# Balancer.net
KiCad netlist of a schematic drawn in EAGLE
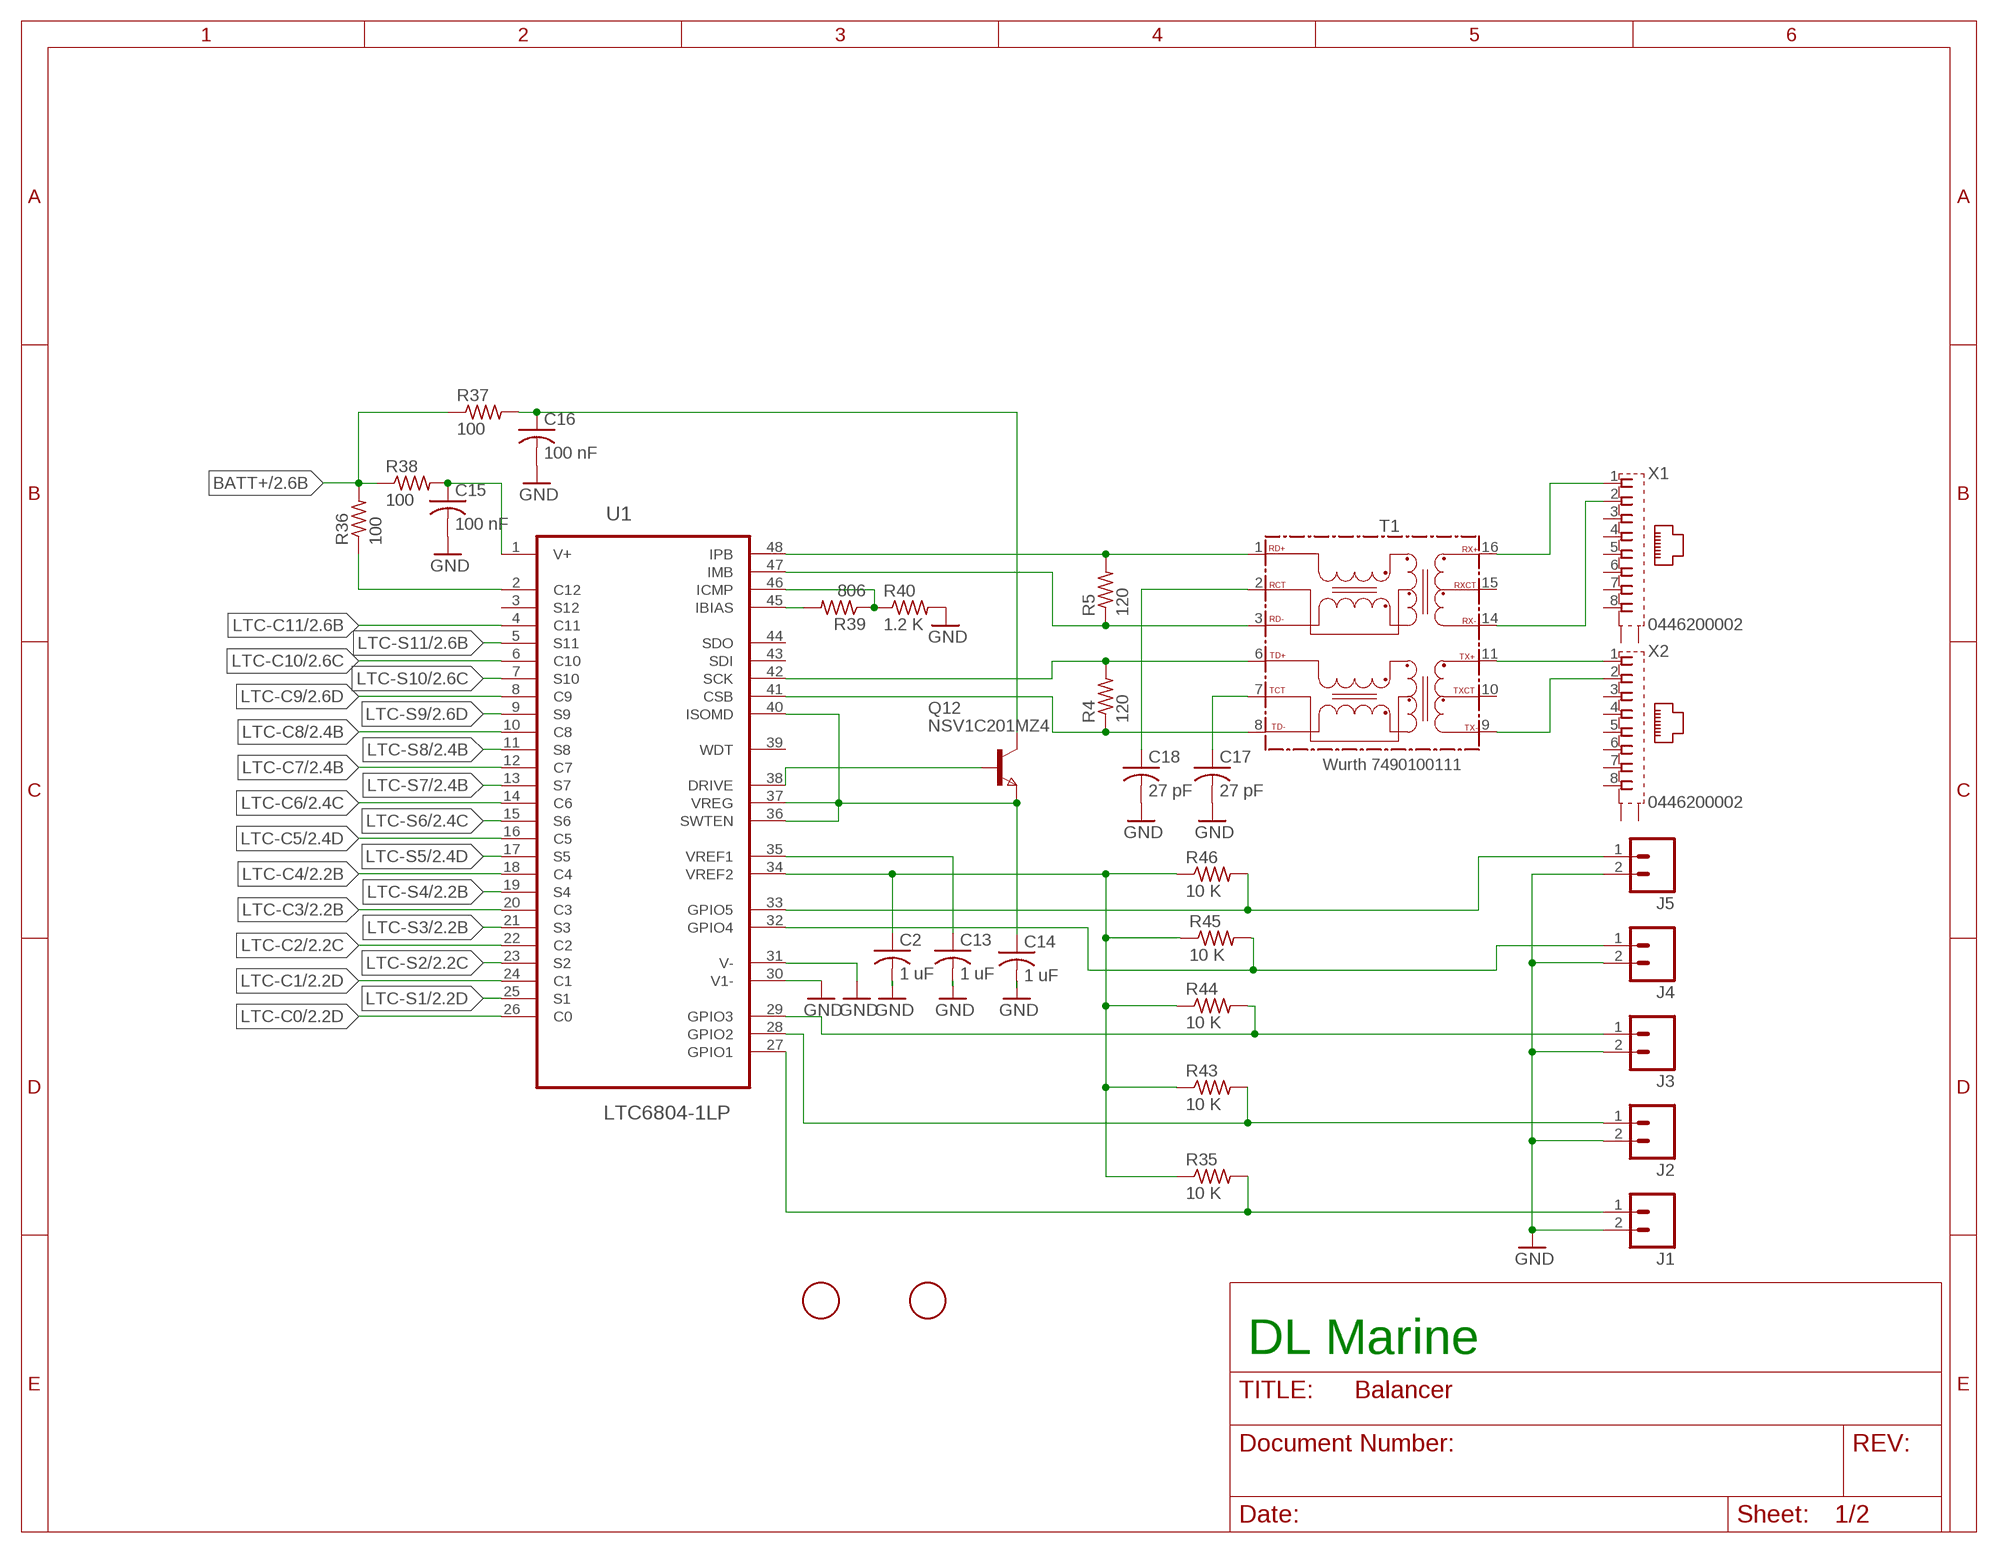
[diagram p0: schematic, sheet 1]
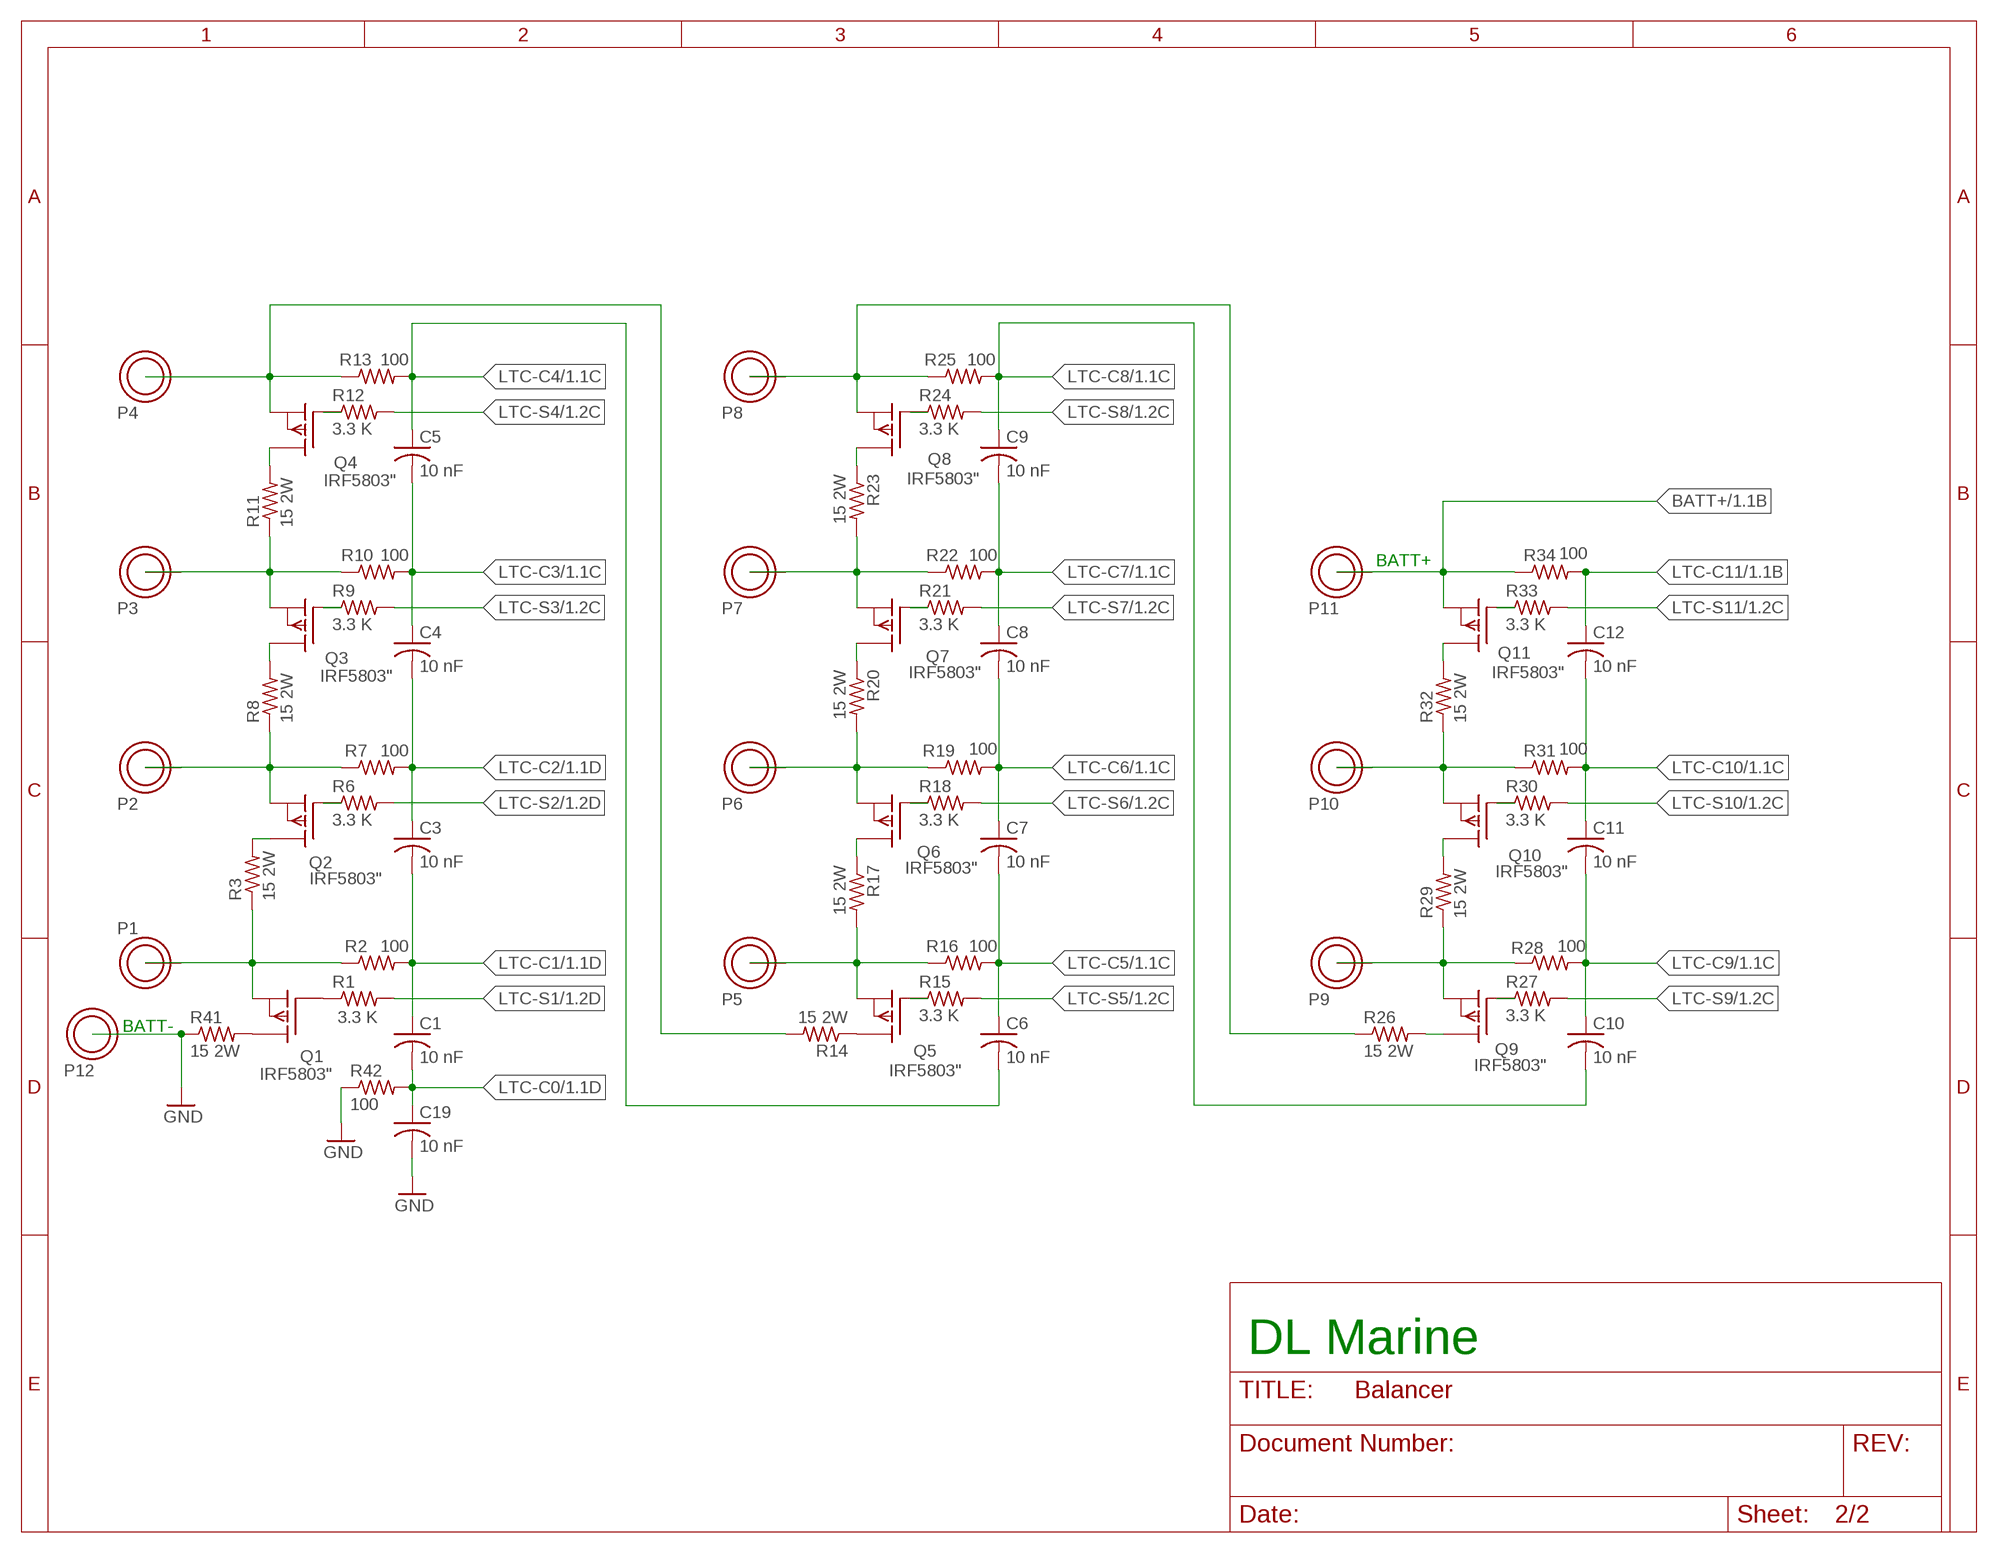
[diagram p1: schematic, sheet 2]

(export (version "E")
  (design (tool "Eeschema 10.0.6"))
  (components
    (comp (ref "C2")
      (value "1 uF")
      (footprint "eagle-import:C0805")
      (libsource (lib "eagle-import") (part "C-USC0805"))
    )
    (comp (ref "C13")
      (value "1 uF")
      (footprint "eagle-import:C0805")
      (libsource (lib "eagle-import") (part "C-USC0805"))
    )
    (comp (ref "C14")
      (value "1 uF")
      (footprint "eagle-import:C0805")
      (libsource (lib "eagle-import") (part "C-USC0805"))
    )
    (comp (ref "C15")
      (value "100 nF")
      (footprint "eagle-import:C0805")
      (libsource (lib "eagle-import") (part "C-USC0805"))
    )
    (comp (ref "C16")
      (value "100 nF")
      (footprint "eagle-import:C0805")
      (libsource (lib "eagle-import") (part "C-USC0805"))
    )
    (comp (ref "C17")
      (value "27 pF")
      (footprint "eagle-import:C0805")
      (libsource (lib "eagle-import") (part "C-USC0805"))
    )
    (comp (ref "C18")
      (value "27 pF")
      (footprint "eagle-import:C0805")
      (libsource (lib "eagle-import") (part "C-USC0805"))
    )
    (comp (ref "J1")
      (value "M02PTH")
      (footprint "eagle-import:1X02")
      (libsource (lib "eagle-import") (part "M02PTH"))
    )
    (comp (ref "J2")
      (value "M02PTH")
      (footprint "eagle-import:1X02")
      (libsource (lib "eagle-import") (part "M02PTH"))
    )
    (comp (ref "J3")
      (value "M02PTH")
      (footprint "eagle-import:1X02")
      (libsource (lib "eagle-import") (part "M02PTH"))
    )
    (comp (ref "J4")
      (value "M02PTH")
      (footprint "eagle-import:1X02")
      (libsource (lib "eagle-import") (part "M02PTH"))
    )
    (comp (ref "J5")
      (value "M02PTH")
      (footprint "eagle-import:1X02")
      (libsource (lib "eagle-import") (part "M02PTH"))
    )
    (comp (ref "Q12")
      (value "NSV1C201MZ4")
      (footprint "eagle-import:SOT223")
      (fields (field (name "MPN") "DJT4031N-13"))
      (libsource (lib "eagle-import") (part "NPNSOT223"))
    )
    (comp (ref "R4")
      (value "120")
      (footprint "eagle-import:R0805")
      (libsource (lib "eagle-import") (part "resistor_R-US_R0805"))
    )
    (comp (ref "R5")
      (value "120")
      (footprint "eagle-import:R0805")
      (libsource (lib "eagle-import") (part "resistor_R-US_R0805"))
    )
    (comp (ref "R35")
      (value "10 K")
      (footprint "eagle-import:R0805")
      (libsource (lib "eagle-import") (part "resistor_R-US_R0805"))
    )
    (comp (ref "R36")
      (value "100")
      (footprint "eagle-import:R0805")
      (libsource (lib "eagle-import") (part "resistor_R-US_R0805"))
    )
    (comp (ref "R37")
      (value "100")
      (footprint "eagle-import:R0805")
      (libsource (lib "eagle-import") (part "resistor_R-US_R0805"))
    )
    (comp (ref "R38")
      (value "100")
      (footprint "eagle-import:R0805")
      (libsource (lib "eagle-import") (part "resistor_R-US_R0805"))
    )
    (comp (ref "R39")
      (value "806")
      (footprint "eagle-import:R0805")
      (libsource (lib "eagle-import") (part "resistor_R-US_R0805"))
    )
    (comp (ref "R40")
      (value "1.2 K")
      (footprint "eagle-import:R0805")
      (libsource (lib "eagle-import") (part "resistor_R-US_R0805"))
    )
    (comp (ref "R43")
      (value "10 K")
      (footprint "eagle-import:R0805")
      (libsource (lib "eagle-import") (part "resistor_R-US_R0805"))
    )
    (comp (ref "R44")
      (value "10 K")
      (footprint "eagle-import:R0805")
      (libsource (lib "eagle-import") (part "resistor_R-US_R0805"))
    )
    (comp (ref "R45")
      (value "10 K")
      (footprint "eagle-import:R0805")
      (libsource (lib "eagle-import") (part "resistor_R-US_R0805"))
    )
    (comp (ref "R46")
      (value "10 K")
      (footprint "eagle-import:R0805")
      (libsource (lib "eagle-import") (part "resistor_R-US_R0805"))
    )
    (comp (ref "T1")
      (value "Wurth 7490100111")
      (footprint "eagle-import:749010011")
      (fields (field (name "MPN") "749010011"))
      (libsource (lib "eagle-import") (part "WE-LAN-10/100-BASE-T,749010011{dblquote}"))
    )
    (comp (ref "U$1")
      (value "FIDUCIAL")
      (footprint "eagle-import:FIDUCIAL_1MM")
      (libsource (lib "eagle-import") (part "FIDUCIAL"))
    )
    (comp (ref "U$2")
      (value "FIDUCIAL")
      (footprint "eagle-import:FIDUCIAL_1MM")
      (libsource (lib "eagle-import") (part "FIDUCIAL"))
    )
    (comp (ref "U1")
      (value "LTC6804-1LP")
      (footprint "eagle-import:SOP50P810X110-48N")
      (libsource (lib "eagle-import") (part "LTC6804-1LP"))
    )
    (comp (ref "X1")
      (value "0446200002")
      (footprint "eagle-import:0446200002")
      (fields (field (name "MF") "MOLEX"))
      (libsource (lib "eagle-import") (part "0446200002"))
    )
    (comp (ref "X2")
      (value "0446200002")
      (footprint "eagle-import:0446200002")
      (fields (field (name "MF") "MOLEX"))
      (libsource (lib "eagle-import") (part "0446200002"))
    )
    (comp (ref "C1")
      (value "10 nF")
      (footprint "eagle-import:C0805")
      (libsource (lib "eagle-import") (part "C-USC0805"))
    )
    (comp (ref "C3")
      (value "10 nF")
      (footprint "eagle-import:C0805")
      (libsource (lib "eagle-import") (part "C-USC0805"))
    )
    (comp (ref "C4")
      (value "10 nF")
      (footprint "eagle-import:C0805")
      (libsource (lib "eagle-import") (part "C-USC0805"))
    )
    (comp (ref "C5")
      (value "10 nF")
      (footprint "eagle-import:C0805")
      (libsource (lib "eagle-import") (part "C-USC0805"))
    )
    (comp (ref "C6")
      (value "10 nF")
      (footprint "eagle-import:C0805")
      (libsource (lib "eagle-import") (part "C-USC0805"))
    )
    (comp (ref "C7")
      (value "10 nF")
      (footprint "eagle-import:C0805")
      (libsource (lib "eagle-import") (part "C-USC0805"))
    )
    (comp (ref "C8")
      (value "10 nF")
      (footprint "eagle-import:C0805")
      (libsource (lib "eagle-import") (part "C-USC0805"))
    )
    (comp (ref "C9")
      (value "10 nF")
      (footprint "eagle-import:C0805")
      (libsource (lib "eagle-import") (part "C-USC0805"))
    )
    (comp (ref "C10")
      (value "10 nF")
      (footprint "eagle-import:C0805")
      (libsource (lib "eagle-import") (part "C-USC0805"))
    )
    (comp (ref "C11")
      (value "10 nF")
      (footprint "eagle-import:C0805")
      (libsource (lib "eagle-import") (part "C-USC0805"))
    )
    (comp (ref "C12")
      (value "10 nF")
      (footprint "eagle-import:C0805")
      (libsource (lib "eagle-import") (part "C-USC0805"))
    )
    (comp (ref "C19")
      (value "10 nF")
      (footprint "eagle-import:C0805")
      (libsource (lib "eagle-import") (part "C-USC0805"))
    )
    (comp (ref "P1")
      (value "CONN-CELL")
      (footprint "eagle-import:CONN-CELL")
      (libsource (lib "eagle-import") (part "CONN-CELL"))
    )
    (comp (ref "P2")
      (value "CONN-CELL")
      (footprint "eagle-import:CONN-CELL")
      (libsource (lib "eagle-import") (part "CONN-CELL"))
    )
    (comp (ref "P3")
      (value "CONN-CELL")
      (footprint "eagle-import:CONN-CELL")
      (libsource (lib "eagle-import") (part "CONN-CELL"))
    )
    (comp (ref "P4")
      (value "CONN-CELL")
      (footprint "eagle-import:CONN-CELL")
      (libsource (lib "eagle-import") (part "CONN-CELL"))
    )
    (comp (ref "P5")
      (value "CONN-CELL")
      (footprint "eagle-import:CONN-CELL")
      (libsource (lib "eagle-import") (part "CONN-CELL"))
    )
    (comp (ref "P6")
      (value "CONN-CELL")
      (footprint "eagle-import:CONN-CELL")
      (libsource (lib "eagle-import") (part "CONN-CELL"))
    )
    (comp (ref "P7")
      (value "CONN-CELL")
      (footprint "eagle-import:CONN-CELL")
      (libsource (lib "eagle-import") (part "CONN-CELL"))
    )
    (comp (ref "P8")
      (value "CONN-CELL")
      (footprint "eagle-import:CONN-CELL")
      (libsource (lib "eagle-import") (part "CONN-CELL"))
    )
    (comp (ref "P9")
      (value "CONN-CELL")
      (footprint "eagle-import:CONN-CELL")
      (libsource (lib "eagle-import") (part "CONN-CELL"))
    )
    (comp (ref "P10")
      (value "CONN-CELL")
      (footprint "eagle-import:CONN-CELL")
      (libsource (lib "eagle-import") (part "CONN-CELL"))
    )
    (comp (ref "P11")
      (value "CONN-CELL")
      (footprint "eagle-import:CONN-CELL")
      (libsource (lib "eagle-import") (part "CONN-CELL"))
    )
    (comp (ref "P12")
      (value "CONN-CELL")
      (footprint "eagle-import:CONN-CELL")
      (libsource (lib "eagle-import") (part "CONN-CELL"))
    )
    (comp (ref "Q1")
      (value "IRF5803\"")
      (footprint "eagle-import:TSOP6_SOT457")
      (libsource (lib "eagle-import") (part "IRF5803{dblquote}"))
    )
    (comp (ref "Q2")
      (value "IRF5803\"")
      (footprint "eagle-import:TSOP6_SOT457")
      (libsource (lib "eagle-import") (part "IRF5803{dblquote}"))
    )
    (comp (ref "Q3")
      (value "IRF5803\"")
      (footprint "eagle-import:TSOP6_SOT457")
      (libsource (lib "eagle-import") (part "IRF5803{dblquote}"))
    )
    (comp (ref "Q4")
      (value "IRF5803\"")
      (footprint "eagle-import:TSOP6_SOT457")
      (libsource (lib "eagle-import") (part "IRF5803{dblquote}"))
    )
    (comp (ref "Q5")
      (value "IRF5803\"")
      (footprint "eagle-import:TSOP6_SOT457")
      (libsource (lib "eagle-import") (part "IRF5803{dblquote}"))
    )
    (comp (ref "Q6")
      (value "IRF5803\"")
      (footprint "eagle-import:TSOP6_SOT457")
      (libsource (lib "eagle-import") (part "IRF5803{dblquote}"))
    )
    (comp (ref "Q7")
      (value "IRF5803\"")
      (footprint "eagle-import:TSOP6_SOT457")
      (libsource (lib "eagle-import") (part "IRF5803{dblquote}"))
    )
    (comp (ref "Q8")
      (value "IRF5803\"")
      (footprint "eagle-import:TSOP6_SOT457")
      (libsource (lib "eagle-import") (part "IRF5803{dblquote}"))
    )
    (comp (ref "Q9")
      (value "IRF5803\"")
      (footprint "eagle-import:TSOP6_SOT457")
      (libsource (lib "eagle-import") (part "IRF5803{dblquote}"))
    )
    (comp (ref "Q10")
      (value "IRF5803\"")
      (footprint "eagle-import:TSOP6_SOT457")
      (libsource (lib "eagle-import") (part "IRF5803{dblquote}"))
    )
    (comp (ref "Q11")
      (value "IRF5803\"")
      (footprint "eagle-import:TSOP6_SOT457")
      (libsource (lib "eagle-import") (part "IRF5803{dblquote}"))
    )
    (comp (ref "R1")
      (value "3.3 K")
      (footprint "eagle-import:R0805")
      (libsource (lib "eagle-import") (part "resistor_R-US_R0805"))
    )
    (comp (ref "R2")
      (value "100")
      (footprint "eagle-import:R0805")
      (libsource (lib "eagle-import") (part "resistor_R-US_R0805"))
    )
    (comp (ref "R3")
      (value "15 2W")
      (footprint "eagle-import:R2512L")
      (libsource (lib "eagle-import") (part "R-US_R2512"))
    )
    (comp (ref "R6")
      (value "3.3 K")
      (footprint "eagle-import:R0805")
      (libsource (lib "eagle-import") (part "resistor_R-US_R0805"))
    )
    (comp (ref "R7")
      (value "100")
      (footprint "eagle-import:R0805")
      (libsource (lib "eagle-import") (part "resistor_R-US_R0805"))
    )
    (comp (ref "R8")
      (value "15 2W")
      (footprint "eagle-import:R2512L")
      (libsource (lib "eagle-import") (part "R-US_R2512"))
    )
    (comp (ref "R9")
      (value "3.3 K")
      (footprint "eagle-import:R0805")
      (libsource (lib "eagle-import") (part "resistor_R-US_R0805"))
    )
    (comp (ref "R10")
      (value "100")
      (footprint "eagle-import:R0805")
      (libsource (lib "eagle-import") (part "resistor_R-US_R0805"))
    )
    (comp (ref "R11")
      (value "15 2W")
      (footprint "eagle-import:R2512L")
      (libsource (lib "eagle-import") (part "R-US_R2512"))
    )
    (comp (ref "R12")
      (value "3.3 K")
      (footprint "eagle-import:R0805")
      (libsource (lib "eagle-import") (part "resistor_R-US_R0805"))
    )
    (comp (ref "R13")
      (value "100")
      (footprint "eagle-import:R0805")
      (libsource (lib "eagle-import") (part "resistor_R-US_R0805"))
    )
    (comp (ref "R14")
      (value "15 2W")
      (footprint "eagle-import:R2512L")
      (libsource (lib "eagle-import") (part "R-US_R2512"))
    )
    (comp (ref "R15")
      (value "3.3 K")
      (footprint "eagle-import:R0805")
      (libsource (lib "eagle-import") (part "resistor_R-US_R0805"))
    )
    (comp (ref "R16")
      (value "100")
      (footprint "eagle-import:R0805")
      (libsource (lib "eagle-import") (part "resistor_R-US_R0805"))
    )
    (comp (ref "R17")
      (value "15 2W")
      (footprint "eagle-import:R2512L")
      (libsource (lib "eagle-import") (part "R-US_R2512"))
    )
    (comp (ref "R18")
      (value "3.3 K")
      (footprint "eagle-import:R0805")
      (libsource (lib "eagle-import") (part "resistor_R-US_R0805"))
    )
    (comp (ref "R19")
      (value "100")
      (footprint "eagle-import:R0805")
      (libsource (lib "eagle-import") (part "resistor_R-US_R0805"))
    )
    (comp (ref "R20")
      (value "15 2W")
      (footprint "eagle-import:R2512L")
      (libsource (lib "eagle-import") (part "R-US_R2512"))
    )
    (comp (ref "R21")
      (value "3.3 K")
      (footprint "eagle-import:R0805")
      (libsource (lib "eagle-import") (part "resistor_R-US_R0805"))
    )
    (comp (ref "R22")
      (value "100")
      (footprint "eagle-import:R0805")
      (libsource (lib "eagle-import") (part "resistor_R-US_R0805"))
    )
    (comp (ref "R23")
      (value "15 2W")
      (footprint "eagle-import:R2512L")
      (libsource (lib "eagle-import") (part "R-US_R2512"))
    )
    (comp (ref "R24")
      (value "3.3 K")
      (footprint "eagle-import:R0805")
      (libsource (lib "eagle-import") (part "resistor_R-US_R0805"))
    )
    (comp (ref "R25")
      (value "100")
      (footprint "eagle-import:R0805")
      (libsource (lib "eagle-import") (part "resistor_R-US_R0805"))
    )
    (comp (ref "R26")
      (value "15 2W")
      (footprint "eagle-import:R2512L")
      (libsource (lib "eagle-import") (part "R-US_R2512"))
    )
    (comp (ref "R27")
      (value "3.3 K")
      (footprint "eagle-import:R0805")
      (libsource (lib "eagle-import") (part "resistor_R-US_R0805"))
    )
    (comp (ref "R28")
      (value "100")
      (footprint "eagle-import:R0805")
      (libsource (lib "eagle-import") (part "resistor_R-US_R0805"))
    )
    (comp (ref "R29")
      (value "15 2W")
      (footprint "eagle-import:R2512L")
      (libsource (lib "eagle-import") (part "R-US_R2512"))
    )
    (comp (ref "R30")
      (value "3.3 K")
      (footprint "eagle-import:R0805")
      (libsource (lib "eagle-import") (part "resistor_R-US_R0805"))
    )
    (comp (ref "R31")
      (value "100")
      (footprint "eagle-import:R0805")
      (libsource (lib "eagle-import") (part "resistor_R-US_R0805"))
    )
    (comp (ref "R32")
      (value "15 2W")
      (footprint "eagle-import:R2512L")
      (libsource (lib "eagle-import") (part "R-US_R2512"))
    )
    (comp (ref "R33")
      (value "3.3 K")
      (footprint "eagle-import:R0805")
      (libsource (lib "eagle-import") (part "resistor_R-US_R0805"))
    )
    (comp (ref "R34")
      (value "100")
      (footprint "eagle-import:R0805")
      (libsource (lib "eagle-import") (part "resistor_R-US_R0805"))
    )
    (comp (ref "R41")
      (value "15 2W")
      (footprint "eagle-import:R2512L")
      (libsource (lib "eagle-import") (part "R-US_R2512"))
    )
    (comp (ref "R42")
      (value "100")
      (footprint "eagle-import:R0805")
      (libsource (lib "eagle-import") (part "resistor_R-US_R0805"))
    )
  )
  (nets
    (net (code "1") (name "BATT+") (class "Default")
      (node (ref "P11") (pin "P$1") (pinfunction "P$1_P$1") (pintype "bidirectional"))
      (node (ref "Q11") (pin "P$4") (pinfunction "S_P$4") (pintype "passive"))
      (node (ref "R34") (pin "1") (pinfunction "1_1") (pintype "passive"))
      (node (ref "R36") (pin "2") (pinfunction "2_2") (pintype "passive"))
      (node (ref "R37") (pin "1") (pinfunction "1_1") (pintype "passive"))
      (node (ref "R38") (pin "1") (pinfunction "1_1") (pintype "passive"))
    )
    (net (code "2") (name "GND") (class "Default")
      (node (ref "C13") (pin "2") (pinfunction "2_2") (pintype "passive"))
      (node (ref "C14") (pin "2") (pinfunction "2_2") (pintype "passive"))
      (node (ref "C15") (pin "2") (pinfunction "2_2") (pintype "passive"))
      (node (ref "C16") (pin "2") (pinfunction "2_2") (pintype "passive"))
      (node (ref "C17") (pin "2") (pinfunction "2_2") (pintype "passive"))
      (node (ref "C18") (pin "2") (pinfunction "2_2") (pintype "passive"))
      (node (ref "C19") (pin "2") (pinfunction "2_2") (pintype "passive"))
      (node (ref "C2") (pin "2") (pinfunction "2_2") (pintype "passive"))
      (node (ref "J1") (pin "2") (pinfunction "2_2") (pintype "passive"))
      (node (ref "J2") (pin "2") (pinfunction "2_2") (pintype "passive"))
      (node (ref "J3") (pin "2") (pinfunction "2_2") (pintype "passive"))
      (node (ref "J4") (pin "2") (pinfunction "2_2") (pintype "passive"))
      (node (ref "J5") (pin "2") (pinfunction "2_2") (pintype "passive"))
      (node (ref "P12") (pin "P$1") (pinfunction "P$1_P$1") (pintype "bidirectional"))
      (node (ref "R40") (pin "2") (pinfunction "2_2") (pintype "passive"))
      (node (ref "R41") (pin "1") (pinfunction "1_1") (pintype "passive"))
      (node (ref "R42") (pin "1") (pinfunction "1_1") (pintype "passive"))
      (node (ref "U1") (pin "30") (pinfunction "V1-_30") (pintype "power_in"))
      (node (ref "U1") (pin "31") (pinfunction "V-_31") (pintype "power_in"))
    )
    (net (code "3") (name "LTC-C0") (class "Default")
      (node (ref "C1") (pin "2") (pinfunction "2_2") (pintype "passive"))
      (node (ref "C19") (pin "1") (pinfunction "1_1") (pintype "passive"))
      (node (ref "R42") (pin "2") (pinfunction "2_2") (pintype "passive"))
      (node (ref "U1") (pin "26") (pinfunction "C0_26") (pintype "input"))
    )
    (net (code "4") (name "LTC-C1") (class "Default")
      (node (ref "C1") (pin "1") (pinfunction "1_1") (pintype "passive"))
      (node (ref "C3") (pin "2") (pinfunction "2_2") (pintype "passive"))
      (node (ref "R2") (pin "2") (pinfunction "2_2") (pintype "passive"))
      (node (ref "U1") (pin "24") (pinfunction "C1_24") (pintype "input"))
    )
    (net (code "5") (name "LTC-C2") (class "Default")
      (node (ref "C3") (pin "1") (pinfunction "1_1") (pintype "passive"))
      (node (ref "C4") (pin "2") (pinfunction "2_2") (pintype "passive"))
      (node (ref "R7") (pin "2") (pinfunction "2_2") (pintype "passive"))
      (node (ref "U1") (pin "22") (pinfunction "C2_22") (pintype "input"))
    )
    (net (code "6") (name "LTC-C3") (class "Default")
      (node (ref "C4") (pin "1") (pinfunction "1_1") (pintype "passive"))
      (node (ref "C5") (pin "2") (pinfunction "2_2") (pintype "passive"))
      (node (ref "R10") (pin "2") (pinfunction "2_2") (pintype "passive"))
      (node (ref "U1") (pin "20") (pinfunction "C3_20") (pintype "input"))
    )
    (net (code "7") (name "LTC-C4") (class "Default")
      (node (ref "C5") (pin "1") (pinfunction "1_1") (pintype "passive"))
      (node (ref "C6") (pin "2") (pinfunction "2_2") (pintype "passive"))
      (node (ref "R13") (pin "2") (pinfunction "2_2") (pintype "passive"))
      (node (ref "U1") (pin "18") (pinfunction "C4_18") (pintype "input"))
    )
    (net (code "8") (name "LTC-C5") (class "Default")
      (node (ref "C6") (pin "1") (pinfunction "1_1") (pintype "passive"))
      (node (ref "C7") (pin "2") (pinfunction "2_2") (pintype "passive"))
      (node (ref "R16") (pin "2") (pinfunction "2_2") (pintype "passive"))
      (node (ref "U1") (pin "16") (pinfunction "C5_16") (pintype "input"))
    )
    (net (code "9") (name "LTC-C6") (class "Default")
      (node (ref "C7") (pin "1") (pinfunction "1_1") (pintype "passive"))
      (node (ref "C8") (pin "2") (pinfunction "2_2") (pintype "passive"))
      (node (ref "R19") (pin "2") (pinfunction "2_2") (pintype "passive"))
      (node (ref "U1") (pin "14") (pinfunction "C6_14") (pintype "input"))
    )
    (net (code "10") (name "LTC-C7") (class "Default")
      (node (ref "C8") (pin "1") (pinfunction "1_1") (pintype "passive"))
      (node (ref "C9") (pin "2") (pinfunction "2_2") (pintype "passive"))
      (node (ref "R22") (pin "2") (pinfunction "2_2") (pintype "passive"))
      (node (ref "U1") (pin "12") (pinfunction "C7_12") (pintype "input"))
    )
    (net (code "11") (name "LTC-C8") (class "Default")
      (node (ref "C10") (pin "2") (pinfunction "2_2") (pintype "passive"))
      (node (ref "C9") (pin "1") (pinfunction "1_1") (pintype "passive"))
      (node (ref "R25") (pin "2") (pinfunction "2_2") (pintype "passive"))
      (node (ref "U1") (pin "10") (pinfunction "C8_10") (pintype "input"))
    )
    (net (code "12") (name "LTC-C9") (class "Default")
      (node (ref "C10") (pin "1") (pinfunction "1_1") (pintype "passive"))
      (node (ref "C11") (pin "2") (pinfunction "2_2") (pintype "passive"))
      (node (ref "R28") (pin "2") (pinfunction "2_2") (pintype "passive"))
      (node (ref "U1") (pin "8") (pinfunction "C9_8") (pintype "input"))
    )
    (net (code "13") (name "LTC-C10") (class "Default")
      (node (ref "C11") (pin "1") (pinfunction "1_1") (pintype "passive"))
      (node (ref "C12") (pin "2") (pinfunction "2_2") (pintype "passive"))
      (node (ref "R31") (pin "2") (pinfunction "2_2") (pintype "passive"))
      (node (ref "U1") (pin "6") (pinfunction "C10_6") (pintype "input"))
    )
    (net (code "14") (name "LTC-C11") (class "Default")
      (node (ref "C12") (pin "1") (pinfunction "1_1") (pintype "passive"))
      (node (ref "R34") (pin "2") (pinfunction "2_2") (pintype "passive"))
      (node (ref "U1") (pin "4") (pinfunction "C11_4") (pintype "input"))
    )
    (net (code "15") (name "LTC-S1") (class "Default")
      (node (ref "R1") (pin "2") (pinfunction "2_2") (pintype "passive"))
      (node (ref "U1") (pin "25") (pinfunction "S1_25") (pintype "output"))
    )
    (net (code "16") (name "LTC-S2") (class "Default")
      (node (ref "R6") (pin "2") (pinfunction "2_2") (pintype "passive"))
      (node (ref "U1") (pin "23") (pinfunction "S2_23") (pintype "output"))
    )
    (net (code "17") (name "LTC-S3") (class "Default")
      (node (ref "R9") (pin "2") (pinfunction "2_2") (pintype "passive"))
      (node (ref "U1") (pin "21") (pinfunction "S3_21") (pintype "output"))
    )
    (net (code "18") (name "LTC-S4") (class "Default")
      (node (ref "R12") (pin "2") (pinfunction "2_2") (pintype "passive"))
      (node (ref "U1") (pin "19") (pinfunction "S4_19") (pintype "output"))
    )
    (net (code "19") (name "LTC-S5") (class "Default")
      (node (ref "R15") (pin "2") (pinfunction "2_2") (pintype "passive"))
      (node (ref "U1") (pin "17") (pinfunction "S5_17") (pintype "output"))
    )
    (net (code "20") (name "LTC-S6") (class "Default")
      (node (ref "R18") (pin "2") (pinfunction "2_2") (pintype "passive"))
      (node (ref "U1") (pin "15") (pinfunction "S6_15") (pintype "output"))
    )
    (net (code "21") (name "LTC-S7") (class "Default")
      (node (ref "R21") (pin "2") (pinfunction "2_2") (pintype "passive"))
      (node (ref "U1") (pin "13") (pinfunction "S7_13") (pintype "output"))
    )
    (net (code "22") (name "LTC-S8") (class "Default")
      (node (ref "R24") (pin "2") (pinfunction "2_2") (pintype "passive"))
      (node (ref "U1") (pin "11") (pinfunction "S8_11") (pintype "output"))
    )
    (net (code "23") (name "LTC-S9") (class "Default")
      (node (ref "R27") (pin "2") (pinfunction "2_2") (pintype "passive"))
      (node (ref "U1") (pin "9") (pinfunction "S9_9") (pintype "output"))
    )
    (net (code "24") (name "LTC-S10") (class "Default")
      (node (ref "R30") (pin "2") (pinfunction "2_2") (pintype "passive"))
      (node (ref "U1") (pin "7") (pinfunction "S10_7") (pintype "output"))
    )
    (net (code "25") (name "LTC-S11") (class "Default")
      (node (ref "R33") (pin "2") (pinfunction "2_2") (pintype "passive"))
      (node (ref "U1") (pin "5") (pinfunction "S11_5") (pintype "output"))
    )
    (net (code "26") (name "Net-(C16-Pad1)") (class "Default")
      (node (ref "C16") (pin "1") (pinfunction "1_1") (pintype "passive"))
      (node (ref "Q12") (pin "2") (pinfunction "C_2") (pintype "passive"))
      (node (ref "Q12") (pin "4") (pinfunction "C_4") (pintype "passive"))
      (node (ref "R37") (pin "2") (pinfunction "2_2") (pintype "passive"))
    )
    (net (code "27") (name "Net-(Q1-D-PadP$1)") (class "Default")
      (node (ref "Q1") (pin "P$1") (pinfunction "D_P$1") (pintype "passive"))
      (node (ref "Q1") (pin "P$2") (pinfunction "D_P$2") (pintype "passive"))
      (node (ref "Q1") (pin "P$5") (pinfunction "D_P$5") (pintype "passive"))
      (node (ref "Q1") (pin "P$6") (pinfunction "D_P$6") (pintype "passive"))
      (node (ref "R41") (pin "2") (pinfunction "2_2") (pintype "passive"))
    )
    (net (code "28") (name "Net-(Q1-G)") (class "Default")
      (node (ref "Q1") (pin "P$3") (pinfunction "G_P$3") (pintype "passive"))
      (node (ref "R1") (pin "1") (pinfunction "1_1") (pintype "passive"))
    )
    (net (code "29") (name "Net-(Q1-S)") (class "Default")
      (node (ref "P1") (pin "P$1") (pinfunction "P$1_P$1") (pintype "bidirectional"))
      (node (ref "Q1") (pin "P$4") (pinfunction "S_P$4") (pintype "passive"))
      (node (ref "R2") (pin "1") (pinfunction "1_1") (pintype "passive"))
      (node (ref "R3") (pin "1") (pinfunction "1_1") (pintype "passive"))
    )
    (net (code "30") (name "Net-(Q2-D-PadP$1)") (class "Default")
      (node (ref "Q2") (pin "P$1") (pinfunction "D_P$1") (pintype "passive"))
      (node (ref "Q2") (pin "P$2") (pinfunction "D_P$2") (pintype "passive"))
      (node (ref "Q2") (pin "P$5") (pinfunction "D_P$5") (pintype "passive"))
      (node (ref "Q2") (pin "P$6") (pinfunction "D_P$6") (pintype "passive"))
      (node (ref "R3") (pin "2") (pinfunction "2_2") (pintype "passive"))
    )
    (net (code "31") (name "Net-(Q2-G)") (class "Default")
      (node (ref "Q2") (pin "P$3") (pinfunction "G_P$3") (pintype "passive"))
      (node (ref "R6") (pin "1") (pinfunction "1_1") (pintype "passive"))
    )
    (net (code "32") (name "Net-(Q2-S)") (class "Default")
      (node (ref "P2") (pin "P$1") (pinfunction "P$1_P$1") (pintype "bidirectional"))
      (node (ref "Q2") (pin "P$4") (pinfunction "S_P$4") (pintype "passive"))
      (node (ref "R7") (pin "1") (pinfunction "1_1") (pintype "passive"))
      (node (ref "R8") (pin "1") (pinfunction "1_1") (pintype "passive"))
    )
    (net (code "33") (name "Net-(Q3-D-PadP$1)") (class "Default")
      (node (ref "Q3") (pin "P$1") (pinfunction "D_P$1") (pintype "passive"))
      (node (ref "Q3") (pin "P$2") (pinfunction "D_P$2") (pintype "passive"))
      (node (ref "Q3") (pin "P$5") (pinfunction "D_P$5") (pintype "passive"))
      (node (ref "Q3") (pin "P$6") (pinfunction "D_P$6") (pintype "passive"))
      (node (ref "R8") (pin "2") (pinfunction "2_2") (pintype "passive"))
    )
    (net (code "34") (name "Net-(Q3-G)") (class "Default")
      (node (ref "Q3") (pin "P$3") (pinfunction "G_P$3") (pintype "passive"))
      (node (ref "R9") (pin "1") (pinfunction "1_1") (pintype "passive"))
    )
    (net (code "35") (name "Net-(Q3-S)") (class "Default")
      (node (ref "P3") (pin "P$1") (pinfunction "P$1_P$1") (pintype "bidirectional"))
      (node (ref "Q3") (pin "P$4") (pinfunction "S_P$4") (pintype "passive"))
      (node (ref "R10") (pin "1") (pinfunction "1_1") (pintype "passive"))
      (node (ref "R11") (pin "1") (pinfunction "1_1") (pintype "passive"))
    )
    (net (code "36") (name "Net-(Q4-D-PadP$1)") (class "Default")
      (node (ref "Q4") (pin "P$1") (pinfunction "D_P$1") (pintype "passive"))
      (node (ref "Q4") (pin "P$2") (pinfunction "D_P$2") (pintype "passive"))
      (node (ref "Q4") (pin "P$5") (pinfunction "D_P$5") (pintype "passive"))
      (node (ref "Q4") (pin "P$6") (pinfunction "D_P$6") (pintype "passive"))
      (node (ref "R11") (pin "2") (pinfunction "2_2") (pintype "passive"))
    )
    (net (code "37") (name "Net-(Q4-G)") (class "Default")
      (node (ref "Q4") (pin "P$3") (pinfunction "G_P$3") (pintype "passive"))
      (node (ref "R12") (pin "1") (pinfunction "1_1") (pintype "passive"))
    )
    (net (code "38") (name "Net-(Q4-S)") (class "Default")
      (node (ref "P4") (pin "P$1") (pinfunction "P$1_P$1") (pintype "bidirectional"))
      (node (ref "Q4") (pin "P$4") (pinfunction "S_P$4") (pintype "passive"))
      (node (ref "R13") (pin "1") (pinfunction "1_1") (pintype "passive"))
      (node (ref "R14") (pin "2") (pinfunction "2_2") (pintype "passive"))
    )
    (net (code "39") (name "Net-(Q5-D-PadP$1)") (class "Default")
      (node (ref "Q5") (pin "P$1") (pinfunction "D_P$1") (pintype "passive"))
      (node (ref "Q5") (pin "P$2") (pinfunction "D_P$2") (pintype "passive"))
      (node (ref "Q5") (pin "P$5") (pinfunction "D_P$5") (pintype "passive"))
      (node (ref "Q5") (pin "P$6") (pinfunction "D_P$6") (pintype "passive"))
      (node (ref "R14") (pin "1") (pinfunction "1_1") (pintype "passive"))
    )
    (net (code "40") (name "Net-(Q5-G)") (class "Default")
      (node (ref "Q5") (pin "P$3") (pinfunction "G_P$3") (pintype "passive"))
      (node (ref "R15") (pin "1") (pinfunction "1_1") (pintype "passive"))
    )
    (net (code "41") (name "Net-(Q5-S)") (class "Default")
      (node (ref "P5") (pin "P$1") (pinfunction "P$1_P$1") (pintype "bidirectional"))
      (node (ref "Q5") (pin "P$4") (pinfunction "S_P$4") (pintype "passive"))
      (node (ref "R16") (pin "1") (pinfunction "1_1") (pintype "passive"))
      (node (ref "R17") (pin "2") (pinfunction "2_2") (pintype "passive"))
    )
    (net (code "42") (name "Net-(Q6-D-PadP$1)") (class "Default")
      (node (ref "Q6") (pin "P$1") (pinfunction "D_P$1") (pintype "passive"))
      (node (ref "Q6") (pin "P$2") (pinfunction "D_P$2") (pintype "passive"))
      (node (ref "Q6") (pin "P$5") (pinfunction "D_P$5") (pintype "passive"))
      (node (ref "Q6") (pin "P$6") (pinfunction "D_P$6") (pintype "passive"))
      (node (ref "R17") (pin "1") (pinfunction "1_1") (pintype "passive"))
    )
    (net (code "43") (name "Net-(Q6-G)") (class "Default")
      (node (ref "Q6") (pin "P$3") (pinfunction "G_P$3") (pintype "passive"))
      (node (ref "R18") (pin "1") (pinfunction "1_1") (pintype "passive"))
    )
    (net (code "44") (name "Net-(Q6-S)") (class "Default")
      (node (ref "P6") (pin "P$1") (pinfunction "P$1_P$1") (pintype "bidirectional"))
      (node (ref "Q6") (pin "P$4") (pinfunction "S_P$4") (pintype "passive"))
      (node (ref "R19") (pin "1") (pinfunction "1_1") (pintype "passive"))
      (node (ref "R20") (pin "2") (pinfunction "2_2") (pintype "passive"))
    )
    (net (code "45") (name "Net-(Q7-D-PadP$1)") (class "Default")
      (node (ref "Q7") (pin "P$1") (pinfunction "D_P$1") (pintype "passive"))
      (node (ref "Q7") (pin "P$2") (pinfunction "D_P$2") (pintype "passive"))
      (node (ref "Q7") (pin "P$5") (pinfunction "D_P$5") (pintype "passive"))
      (node (ref "Q7") (pin "P$6") (pinfunction "D_P$6") (pintype "passive"))
      (node (ref "R20") (pin "1") (pinfunction "1_1") (pintype "passive"))
    )
    (net (code "46") (name "Net-(Q7-G)") (class "Default")
      (node (ref "Q7") (pin "P$3") (pinfunction "G_P$3") (pintype "passive"))
      (node (ref "R21") (pin "1") (pinfunction "1_1") (pintype "passive"))
    )
    (net (code "47") (name "Net-(Q7-S)") (class "Default")
      (node (ref "P7") (pin "P$1") (pinfunction "P$1_P$1") (pintype "bidirectional"))
      (node (ref "Q7") (pin "P$4") (pinfunction "S_P$4") (pintype "passive"))
      (node (ref "R22") (pin "1") (pinfunction "1_1") (pintype "passive"))
      (node (ref "R23") (pin "2") (pinfunction "2_2") (pintype "passive"))
    )
    (net (code "48") (name "Net-(Q8-D-PadP$1)") (class "Default")
      (node (ref "Q8") (pin "P$1") (pinfunction "D_P$1") (pintype "passive"))
      (node (ref "Q8") (pin "P$2") (pinfunction "D_P$2") (pintype "passive"))
      (node (ref "Q8") (pin "P$5") (pinfunction "D_P$5") (pintype "passive"))
      (node (ref "Q8") (pin "P$6") (pinfunction "D_P$6") (pintype "passive"))
      (node (ref "R23") (pin "1") (pinfunction "1_1") (pintype "passive"))
    )
    (net (code "49") (name "Net-(Q8-G)") (class "Default")
      (node (ref "Q8") (pin "P$3") (pinfunction "G_P$3") (pintype "passive"))
      (node (ref "R24") (pin "1") (pinfunction "1_1") (pintype "passive"))
    )
    (net (code "50") (name "Net-(Q8-S)") (class "Default")
      (node (ref "P8") (pin "P$1") (pinfunction "P$1_P$1") (pintype "bidirectional"))
      (node (ref "Q8") (pin "P$4") (pinfunction "S_P$4") (pintype "passive"))
      (node (ref "R25") (pin "1") (pinfunction "1_1") (pintype "passive"))
      (node (ref "R26") (pin "1") (pinfunction "1_1") (pintype "passive"))
    )
    (net (code "51") (name "Net-(Q9-D-PadP$1)") (class "Default")
      (node (ref "Q9") (pin "P$1") (pinfunction "D_P$1") (pintype "passive"))
      (node (ref "Q9") (pin "P$2") (pinfunction "D_P$2") (pintype "passive"))
      (node (ref "Q9") (pin "P$5") (pinfunction "D_P$5") (pintype "passive"))
      (node (ref "Q9") (pin "P$6") (pinfunction "D_P$6") (pintype "passive"))
      (node (ref "R26") (pin "2") (pinfunction "2_2") (pintype "passive"))
    )
    (net (code "52") (name "Net-(Q9-G)") (class "Default")
      (node (ref "Q9") (pin "P$3") (pinfunction "G_P$3") (pintype "passive"))
      (node (ref "R27") (pin "1") (pinfunction "1_1") (pintype "passive"))
    )
    (net (code "53") (name "Net-(Q9-S)") (class "Default")
      (node (ref "P9") (pin "P$1") (pinfunction "P$1_P$1") (pintype "bidirectional"))
      (node (ref "Q9") (pin "P$4") (pinfunction "S_P$4") (pintype "passive"))
      (node (ref "R28") (pin "1") (pinfunction "1_1") (pintype "passive"))
      (node (ref "R29") (pin "1") (pinfunction "1_1") (pintype "passive"))
    )
    (net (code "54") (name "Net-(Q10-D-PadP$1)") (class "Default")
      (node (ref "Q10") (pin "P$1") (pinfunction "D_P$1") (pintype "passive"))
      (node (ref "Q10") (pin "P$2") (pinfunction "D_P$2") (pintype "passive"))
      (node (ref "Q10") (pin "P$5") (pinfunction "D_P$5") (pintype "passive"))
      (node (ref "Q10") (pin "P$6") (pinfunction "D_P$6") (pintype "passive"))
      (node (ref "R29") (pin "2") (pinfunction "2_2") (pintype "passive"))
    )
    (net (code "55") (name "Net-(Q10-G)") (class "Default")
      (node (ref "Q10") (pin "P$3") (pinfunction "G_P$3") (pintype "passive"))
      (node (ref "R30") (pin "1") (pinfunction "1_1") (pintype "passive"))
    )
    (net (code "56") (name "Net-(Q10-S)") (class "Default")
      (node (ref "P10") (pin "P$1") (pinfunction "P$1_P$1") (pintype "bidirectional"))
      (node (ref "Q10") (pin "P$4") (pinfunction "S_P$4") (pintype "passive"))
      (node (ref "R31") (pin "1") (pinfunction "1_1") (pintype "passive"))
      (node (ref "R32") (pin "1") (pinfunction "1_1") (pintype "passive"))
    )
    (net (code "57") (name "Net-(Q11-D-PadP$1)") (class "Default")
      (node (ref "Q11") (pin "P$1") (pinfunction "D_P$1") (pintype "passive"))
      (node (ref "Q11") (pin "P$2") (pinfunction "D_P$2") (pintype "passive"))
      (node (ref "Q11") (pin "P$5") (pinfunction "D_P$5") (pintype "passive"))
      (node (ref "Q11") (pin "P$6") (pinfunction "D_P$6") (pintype "passive"))
      (node (ref "R32") (pin "2") (pinfunction "2_2") (pintype "passive"))
    )
    (net (code "58") (name "Net-(Q11-G)") (class "Default")
      (node (ref "Q11") (pin "P$3") (pinfunction "G_P$3") (pintype "passive"))
      (node (ref "R33") (pin "1") (pinfunction "1_1") (pintype "passive"))
    )
    (net (code "59") (name "Net-(Q12-B)") (class "Default")
      (node (ref "Q12") (pin "1") (pinfunction "B_1") (pintype "passive"))
      (node (ref "U1") (pin "38") (pinfunction "DRIVE_38") (pintype "output"))
    )
    (net (code "60") (name "Net-(Q12-E)") (class "Default")
      (node (ref "C14") (pin "1") (pinfunction "1_1") (pintype "passive"))
      (node (ref "Q12") (pin "3") (pinfunction "E_3") (pintype "passive"))
      (node (ref "U1") (pin "36") (pinfunction "SWTEN_36") (pintype "bidirectional"))
      (node (ref "U1") (pin "37") (pinfunction "VREG_37") (pintype "output"))
      (node (ref "U1") (pin "40") (pinfunction "ISOMD_40") (pintype "input"))
    )
    (net (code "61") (name "Net-(T1-RCT)") (class "Default")
      (node (ref "C18") (pin "1") (pinfunction "1_1") (pintype "passive"))
      (node (ref "T1") (pin "2") (pinfunction "RCT_2") (pintype "bidirectional"))
    )
    (net (code "62") (name "Net-(T1-RD+)") (class "Default")
      (node (ref "R5") (pin "2") (pinfunction "2_2") (pintype "passive"))
      (node (ref "T1") (pin "1") (pinfunction "RD+_1") (pintype "bidirectional"))
      (node (ref "U1") (pin "48") (pinfunction "IPB_48") (pintype "output"))
    )
    (net (code "63") (name "Net-(T1-RD-)") (class "Default")
      (node (ref "R5") (pin "1") (pinfunction "1_1") (pintype "passive"))
      (node (ref "T1") (pin "3") (pinfunction "RD-_3") (pintype "bidirectional"))
      (node (ref "U1") (pin "47") (pinfunction "IMB_47") (pintype "output"))
    )
    (net (code "64") (name "Net-(T1-RX+)") (class "Default")
      (node (ref "T1") (pin "16") (pinfunction "RX+_16") (pintype "bidirectional"))
      (node (ref "X1") (pin "1") (pinfunction "1_1") (pintype "passive"))
    )
    (net (code "65") (name "Net-(T1-RX-)") (class "Default")
      (node (ref "T1") (pin "14") (pinfunction "RX-_14") (pintype "bidirectional"))
      (node (ref "X1") (pin "2") (pinfunction "2_2") (pintype "passive"))
    )
    (net (code "66") (name "Net-(T1-TCT)") (class "Default")
      (node (ref "C17") (pin "1") (pinfunction "1_1") (pintype "passive"))
      (node (ref "T1") (pin "7") (pinfunction "TCT_7") (pintype "bidirectional"))
    )
    (net (code "67") (name "Net-(T1-TD+)") (class "Default")
      (node (ref "R4") (pin "2") (pinfunction "2_2") (pintype "passive"))
      (node (ref "T1") (pin "6") (pinfunction "TD+_6") (pintype "bidirectional"))
      (node (ref "U1") (pin "42") (pinfunction "SCK_42") (pintype "input"))
    )
    (net (code "68") (name "Net-(T1-TD-)") (class "Default")
      (node (ref "R4") (pin "1") (pinfunction "1_1") (pintype "passive"))
      (node (ref "T1") (pin "8") (pinfunction "TD-_8") (pintype "bidirectional"))
      (node (ref "U1") (pin "41") (pinfunction "CSB_41") (pintype "output"))
    )
    (net (code "69") (name "Net-(T1-TX+)") (class "Default")
      (node (ref "T1") (pin "11") (pinfunction "TX+_11") (pintype "bidirectional"))
      (node (ref "X2") (pin "1") (pinfunction "1_1") (pintype "passive"))
    )
    (net (code "70") (name "Net-(T1-TX-)") (class "Default")
      (node (ref "T1") (pin "9") (pinfunction "TX-_9") (pintype "bidirectional"))
      (node (ref "X2") (pin "2") (pinfunction "2_2") (pintype "passive"))
    )
    (net (code "71") (name "Net-(U1-C12)") (class "Default")
      (node (ref "R36") (pin "1") (pinfunction "1_1") (pintype "passive"))
      (node (ref "U1") (pin "2") (pinfunction "C12_2") (pintype "input"))
    )
    (net (code "72") (name "Net-(U1-GPIO1)") (class "Default")
      (node (ref "J1") (pin "1") (pinfunction "1_1") (pintype "passive"))
      (node (ref "R35") (pin "2") (pinfunction "2_2") (pintype "passive"))
      (node (ref "U1") (pin "27") (pinfunction "GPIO1_27") (pintype "bidirectional"))
    )
    (net (code "73") (name "Net-(U1-GPIO2)") (class "Default")
      (node (ref "J2") (pin "1") (pinfunction "1_1") (pintype "passive"))
      (node (ref "R43") (pin "2") (pinfunction "2_2") (pintype "passive"))
      (node (ref "U1") (pin "28") (pinfunction "GPIO2_28") (pintype "bidirectional"))
    )
    (net (code "74") (name "Net-(U1-GPIO3)") (class "Default")
      (node (ref "J3") (pin "1") (pinfunction "1_1") (pintype "passive"))
      (node (ref "R44") (pin "2") (pinfunction "2_2") (pintype "passive"))
      (node (ref "U1") (pin "29") (pinfunction "GPIO3_29") (pintype "bidirectional"))
    )
    (net (code "75") (name "Net-(U1-GPIO4)") (class "Default")
      (node (ref "J4") (pin "1") (pinfunction "1_1") (pintype "passive"))
      (node (ref "R45") (pin "2") (pinfunction "2_2") (pintype "passive"))
      (node (ref "U1") (pin "32") (pinfunction "GPIO4_32") (pintype "bidirectional"))
    )
    (net (code "76") (name "Net-(U1-GPIO5)") (class "Default")
      (node (ref "J5") (pin "1") (pinfunction "1_1") (pintype "passive"))
      (node (ref "R46") (pin "2") (pinfunction "2_2") (pintype "passive"))
      (node (ref "U1") (pin "33") (pinfunction "GPIO5_33") (pintype "bidirectional"))
    )
    (net (code "77") (name "Net-(U1-IBIAS)") (class "Default")
      (node (ref "R39") (pin "2") (pinfunction "2_2") (pintype "passive"))
      (node (ref "U1") (pin "45") (pinfunction "IBIAS_45") (pintype "input"))
    )
    (net (code "78") (name "Net-(U1-ICMP)") (class "Default")
      (node (ref "R39") (pin "1") (pinfunction "1_1") (pintype "passive"))
      (node (ref "R40") (pin "1") (pinfunction "1_1") (pintype "passive"))
      (node (ref "U1") (pin "46") (pinfunction "ICMP_46") (pintype "input"))
    )
    (net (code "79") (name "Net-(U1-V+)") (class "Default")
      (node (ref "C15") (pin "1") (pinfunction "1_1") (pintype "passive"))
      (node (ref "R38") (pin "2") (pinfunction "2_2") (pintype "passive"))
      (node (ref "U1") (pin "1") (pinfunction "V+_1") (pintype "power_in"))
    )
    (net (code "80") (name "Net-(U1-VREF1)") (class "Default")
      (node (ref "C13") (pin "1") (pinfunction "1_1") (pintype "passive"))
      (node (ref "U1") (pin "35") (pinfunction "VREF1_35") (pintype "output"))
    )
    (net (code "81") (name "Net-(U1-VREF2)") (class "Default")
      (node (ref "C2") (pin "1") (pinfunction "1_1") (pintype "passive"))
      (node (ref "R35") (pin "1") (pinfunction "1_1") (pintype "passive"))
      (node (ref "R43") (pin "1") (pinfunction "1_1") (pintype "passive"))
      (node (ref "R44") (pin "1") (pinfunction "1_1") (pintype "passive"))
      (node (ref "R45") (pin "1") (pinfunction "1_1") (pintype "passive"))
      (node (ref "R46") (pin "1") (pinfunction "1_1") (pintype "passive"))
      (node (ref "U1") (pin "34") (pinfunction "VREF2_34") (pintype "output"))
    )
    (net (code "82") (name "unconnected-(T1-RXCT-Pad15)") (class "Default")
      (node (ref "T1") (pin "15") (pinfunction "RXCT_15") (pintype "bidirectional"))
    )
    (net (code "83") (name "unconnected-(T1-TXCT-Pad10)") (class "Default")
      (node (ref "T1") (pin "10") (pinfunction "TXCT_10") (pintype "bidirectional"))
    )
    (net (code "84") (name "unconnected-(U1-S12-Pad3)") (class "Default")
      (node (ref "U1") (pin "3") (pinfunction "S12_3") (pintype "output"))
    )
    (net (code "85") (name "unconnected-(U1-SDI-Pad43)") (class "Default")
      (node (ref "U1") (pin "43") (pinfunction "SDI_43") (pintype "input"))
    )
    (net (code "86") (name "unconnected-(U1-SDO-Pad44)") (class "Default")
      (node (ref "U1") (pin "44") (pinfunction "SDO_44") (pintype "output"))
    )
    (net (code "87") (name "unconnected-(U1-WDT-Pad39)") (class "Default")
      (node (ref "U1") (pin "39") (pinfunction "WDT_39") (pintype "output"))
    )
    (net (code "88") (name "unconnected-(X1-Pad3)") (class "Default")
      (node (ref "X1") (pin "3") (pinfunction "3_3") (pintype "passive"))
    )
    (net (code "89") (name "unconnected-(X1-Pad4)") (class "Default")
      (node (ref "X1") (pin "4") (pinfunction "4_4") (pintype "passive"))
    )
    (net (code "90") (name "unconnected-(X1-Pad5)") (class "Default")
      (node (ref "X1") (pin "5") (pinfunction "5_5") (pintype "passive"))
    )
    (net (code "91") (name "unconnected-(X1-Pad6)") (class "Default")
      (node (ref "X1") (pin "6") (pinfunction "6_6") (pintype "passive"))
    )
    (net (code "92") (name "unconnected-(X1-Pad7)") (class "Default")
      (node (ref "X1") (pin "7") (pinfunction "7_7") (pintype "passive"))
    )
    (net (code "93") (name "unconnected-(X1-Pad8)") (class "Default")
      (node (ref "X1") (pin "8") (pinfunction "8_8") (pintype "passive"))
    )
    (net (code "94") (name "unconnected-(X1-S1-PadS@1)") (class "Default")
      (node (ref "X1") (pin "S@1") (pinfunction "S1_S@1") (pintype "passive"))
    )
    (net (code "95") (name "unconnected-(X1-S2-PadS@2)") (class "Default")
      (node (ref "X1") (pin "S@2") (pinfunction "S2_S@2") (pintype "passive"))
    )
    (net (code "96") (name "unconnected-(X2-Pad3)") (class "Default")
      (node (ref "X2") (pin "3") (pinfunction "3_3") (pintype "passive"))
    )
    (net (code "97") (name "unconnected-(X2-Pad4)") (class "Default")
      (node (ref "X2") (pin "4") (pinfunction "4_4") (pintype "passive"))
    )
    (net (code "98") (name "unconnected-(X2-Pad5)") (class "Default")
      (node (ref "X2") (pin "5") (pinfunction "5_5") (pintype "passive"))
    )
    (net (code "99") (name "unconnected-(X2-Pad6)") (class "Default")
      (node (ref "X2") (pin "6") (pinfunction "6_6") (pintype "passive"))
    )
    (net (code "100") (name "unconnected-(X2-Pad7)") (class "Default")
      (node (ref "X2") (pin "7") (pinfunction "7_7") (pintype "passive"))
    )
    (net (code "101") (name "unconnected-(X2-Pad8)") (class "Default")
      (node (ref "X2") (pin "8") (pinfunction "8_8") (pintype "passive"))
    )
    (net (code "102") (name "unconnected-(X2-S1-PadS@1)") (class "Default")
      (node (ref "X2") (pin "S@1") (pinfunction "S1_S@1") (pintype "passive"))
    )
    (net (code "103") (name "unconnected-(X2-S2-PadS@2)") (class "Default")
      (node (ref "X2") (pin "S@2") (pinfunction "S2_S@2") (pintype "passive"))
    )
  )
)
